# v1_0.net
KiCad netlist of a schematic drawn in Altium Designer
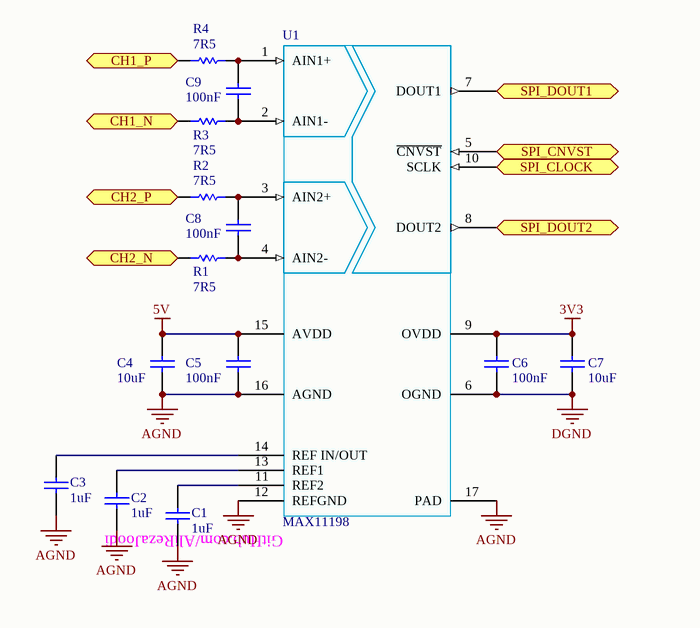
[diagram p0: v1.0.SchDoc]

(export (version "E")
  (design (tool "Eeschema 10.0.6"))
  (components
    (comp (ref "C1")
      (value "1uF")
      (footprint "Capacitor_Ceramic:SMD_0805")
      (description "Capacitor, Ceramic Multilayer, 25V, 10%")
      (libsource (lib "General") (part "Capacitor_Ceramic"))
    )
    (comp (ref "C2")
      (value "1uF")
      (footprint "Capacitor_Ceramic:SMD_0805")
      (description "Capacitor, Ceramic Multilayer, 25V, 10%")
      (libsource (lib "General") (part "Capacitor_Ceramic"))
    )
    (comp (ref "C3")
      (value "1uF")
      (footprint "Capacitor_Ceramic:SMD_0805")
      (description "Capacitor, Ceramic Multilayer, 25V, 10%")
      (libsource (lib "General") (part "Capacitor_Ceramic"))
    )
    (comp (ref "C4")
      (value "10uF")
      (footprint "Capacitor_Ceramic:SMD_0805")
      (description "Capacitor, Ceramic Multilayer, 25V, 10%")
      (libsource (lib "General") (part "Capacitor_Ceramic"))
    )
    (comp (ref "C5")
      (value "100nF")
      (footprint "Capacitor_Ceramic:SMD_0805")
      (description "Capacitor, Ceramic Multilayer, 25V, 10%")
      (libsource (lib "General") (part "Capacitor_Ceramic"))
    )
    (comp (ref "C6")
      (value "100nF")
      (footprint "Capacitor_Ceramic:SMD_0805")
      (description "Capacitor, Ceramic Multilayer, 25V, 10%")
      (libsource (lib "General") (part "Capacitor_Ceramic"))
    )
    (comp (ref "C7")
      (value "10uF")
      (footprint "Capacitor_Ceramic:SMD_0805")
      (description "Capacitor, Ceramic Multilayer, 25V, 10%")
      (libsource (lib "General") (part "Capacitor_Ceramic"))
    )
    (comp (ref "C8")
      (value "100nF")
      (footprint "Capacitor_Ceramic:SMD_0805")
      (description "Capacitor, Ceramic Multilayer, 25V, 10%")
      (libsource (lib "General") (part "Capacitor_Ceramic"))
    )
    (comp (ref "C9")
      (value "100nF")
      (footprint "Capacitor_Ceramic:SMD_0805")
      (description "Capacitor, Ceramic Multilayer, 25V, 10%")
      (libsource (lib "General") (part "Capacitor_Ceramic"))
    )
    (comp (ref "R1")
      (value "7R5")
      (footprint "SMD_0805")
      (description "Resistor, 1/8W, 5%")
      (libsource (lib "General") (part "Resistor"))
    )
    (comp (ref "R2")
      (value "7R5")
      (footprint "SMD_0805")
      (description "Resistor, 1/8W, 5%")
      (libsource (lib "General") (part "Resistor"))
    )
    (comp (ref "R3")
      (value "7R5")
      (footprint "SMD_0805")
      (description "Resistor, 1/8W, 5%")
      (libsource (lib "General") (part "Resistor"))
    )
    (comp (ref "R4")
      (value "7R5")
      (footprint "SMD_0805")
      (description "Resistor, 1/8W, 5%")
      (libsource (lib "General") (part "Resistor"))
    )
    (comp (ref "U1")
      (value "MAX11198")
      (footprint "16TDFN")
      (description "IC, Dual ADCs")
      (fields
        (field (name "MANUFACTURER") "Analog Devices / Maxim Integrated")
        (field (name "PART NUMBER") "MAX11198ATE+T")
      )
      (libsource (lib "IC") (part "MAX1119x"))
    )
  )
  (nets
    (net (code "1") (name "/CH1_N") (class "Default")
      (node (ref "R3") (pin "1") (pinfunction "1_1") (pintype "passive"))
    )
    (net (code "2") (name "/CH1_P") (class "Default")
      (node (ref "R4") (pin "1") (pinfunction "1_1") (pintype "passive"))
    )
    (net (code "3") (name "/CH2_N") (class "Default")
      (node (ref "R1") (pin "1") (pinfunction "1_1") (pintype "passive"))
    )
    (net (code "4") (name "/CH2_P") (class "Default")
      (node (ref "R2") (pin "1") (pinfunction "1_1") (pintype "passive"))
    )
    (net (code "5") (name "/SPI_CLOCK") (class "Default")
      (node (ref "U1") (pin "10") (pinfunction "SCLK_10") (pintype "input"))
    )
    (net (code "6") (name "/SPI_CNVST") (class "Default")
      (node (ref "U1") (pin "5") (pinfunction "~{CNVST}_5") (pintype "input"))
    )
    (net (code "7") (name "/SPI_DOUT1") (class "Default")
      (node (ref "U1") (pin "7") (pinfunction "DOUT1_7") (pintype "output"))
    )
    (net (code "8") (name "/SPI_DOUT2") (class "Default")
      (node (ref "U1") (pin "8") (pinfunction "DOUT2_8") (pintype "output"))
    )
    (net (code "9") (name "3V3") (class "Default")
      (node (ref "C6") (pin "2") (pinfunction "2_2") (pintype "passive"))
      (node (ref "C7") (pin "2") (pinfunction "2_2") (pintype "passive"))
      (node (ref "U1") (pin "9") (pinfunction "OVDD_9") (pintype "power_in"))
    )
    (net (code "10") (name "5V") (class "Default")
      (node (ref "C4") (pin "2") (pinfunction "2_2") (pintype "passive"))
      (node (ref "C5") (pin "2") (pinfunction "2_2") (pintype "passive"))
      (node (ref "U1") (pin "15") (pinfunction "AVDD_15") (pintype "power_in"))
    )
    (net (code "11") (name "AGND") (class "Default")
      (node (ref "C1") (pin "2") (pinfunction "2_2") (pintype "passive"))
      (node (ref "C2") (pin "2") (pinfunction "2_2") (pintype "passive"))
      (node (ref "C3") (pin "2") (pinfunction "2_2") (pintype "passive"))
      (node (ref "C4") (pin "1") (pinfunction "1_1") (pintype "passive"))
      (node (ref "C5") (pin "1") (pinfunction "1_1") (pintype "passive"))
      (node (ref "U1") (pin "12") (pinfunction "REFGND_12") (pintype "power_in"))
      (node (ref "U1") (pin "16") (pinfunction "AGND_16") (pintype "power_in"))
      (node (ref "U1") (pin "17") (pinfunction "PAD_17") (pintype "power_in"))
    )
    (net (code "12") (name "DGND") (class "Default")
      (node (ref "C6") (pin "1") (pinfunction "1_1") (pintype "passive"))
      (node (ref "C7") (pin "1") (pinfunction "1_1") (pintype "passive"))
      (node (ref "U1") (pin "6") (pinfunction "OGND_6") (pintype "power_in"))
    )
    (net (code "13") (name "Net-(U1-AIN1+)") (class "Default")
      (node (ref "C9") (pin "2") (pinfunction "2_2") (pintype "passive"))
      (node (ref "R4") (pin "2") (pinfunction "2_2") (pintype "passive"))
      (node (ref "U1") (pin "1") (pinfunction "AIN1+_1") (pintype "input"))
    )
    (net (code "14") (name "Net-(U1-AIN1-)") (class "Default")
      (node (ref "C9") (pin "1") (pinfunction "1_1") (pintype "passive"))
      (node (ref "R3") (pin "2") (pinfunction "2_2") (pintype "passive"))
      (node (ref "U1") (pin "2") (pinfunction "AIN1-_2") (pintype "input"))
    )
    (net (code "15") (name "Net-(U1-AIN2+)") (class "Default")
      (node (ref "C8") (pin "2") (pinfunction "2_2") (pintype "passive"))
      (node (ref "R2") (pin "2") (pinfunction "2_2") (pintype "passive"))
      (node (ref "U1") (pin "3") (pinfunction "AIN2+_3") (pintype "input"))
    )
    (net (code "16") (name "Net-(U1-AIN2-)") (class "Default")
      (node (ref "C8") (pin "1") (pinfunction "1_1") (pintype "passive"))
      (node (ref "R1") (pin "2") (pinfunction "2_2") (pintype "passive"))
      (node (ref "U1") (pin "4") (pinfunction "AIN2-_4") (pintype "input"))
    )
    (net (code "17") (name "Net-(U1-REF1)") (class "Default")
      (node (ref "C2") (pin "1") (pinfunction "1_1") (pintype "passive"))
      (node (ref "U1") (pin "13") (pinfunction "REF1_13") (pintype "power_in"))
    )
    (net (code "18") (name "Net-(U1-REF2)") (class "Default")
      (node (ref "C1") (pin "1") (pinfunction "1_1") (pintype "passive"))
      (node (ref "U1") (pin "11") (pinfunction "REF2_11") (pintype "power_in"))
    )
    (net (code "19") (name "Net-(U1-REF_IN{slash}OUT)") (class "Default")
      (node (ref "C3") (pin "1") (pinfunction "1_1") (pintype "passive"))
      (node (ref "U1") (pin "14") (pinfunction "REF_IN/OUT_14") (pintype "passive"))
    )
  )
)
